# anglesenseor.net
KiCad netlist of a schematic drawn in EAGLE
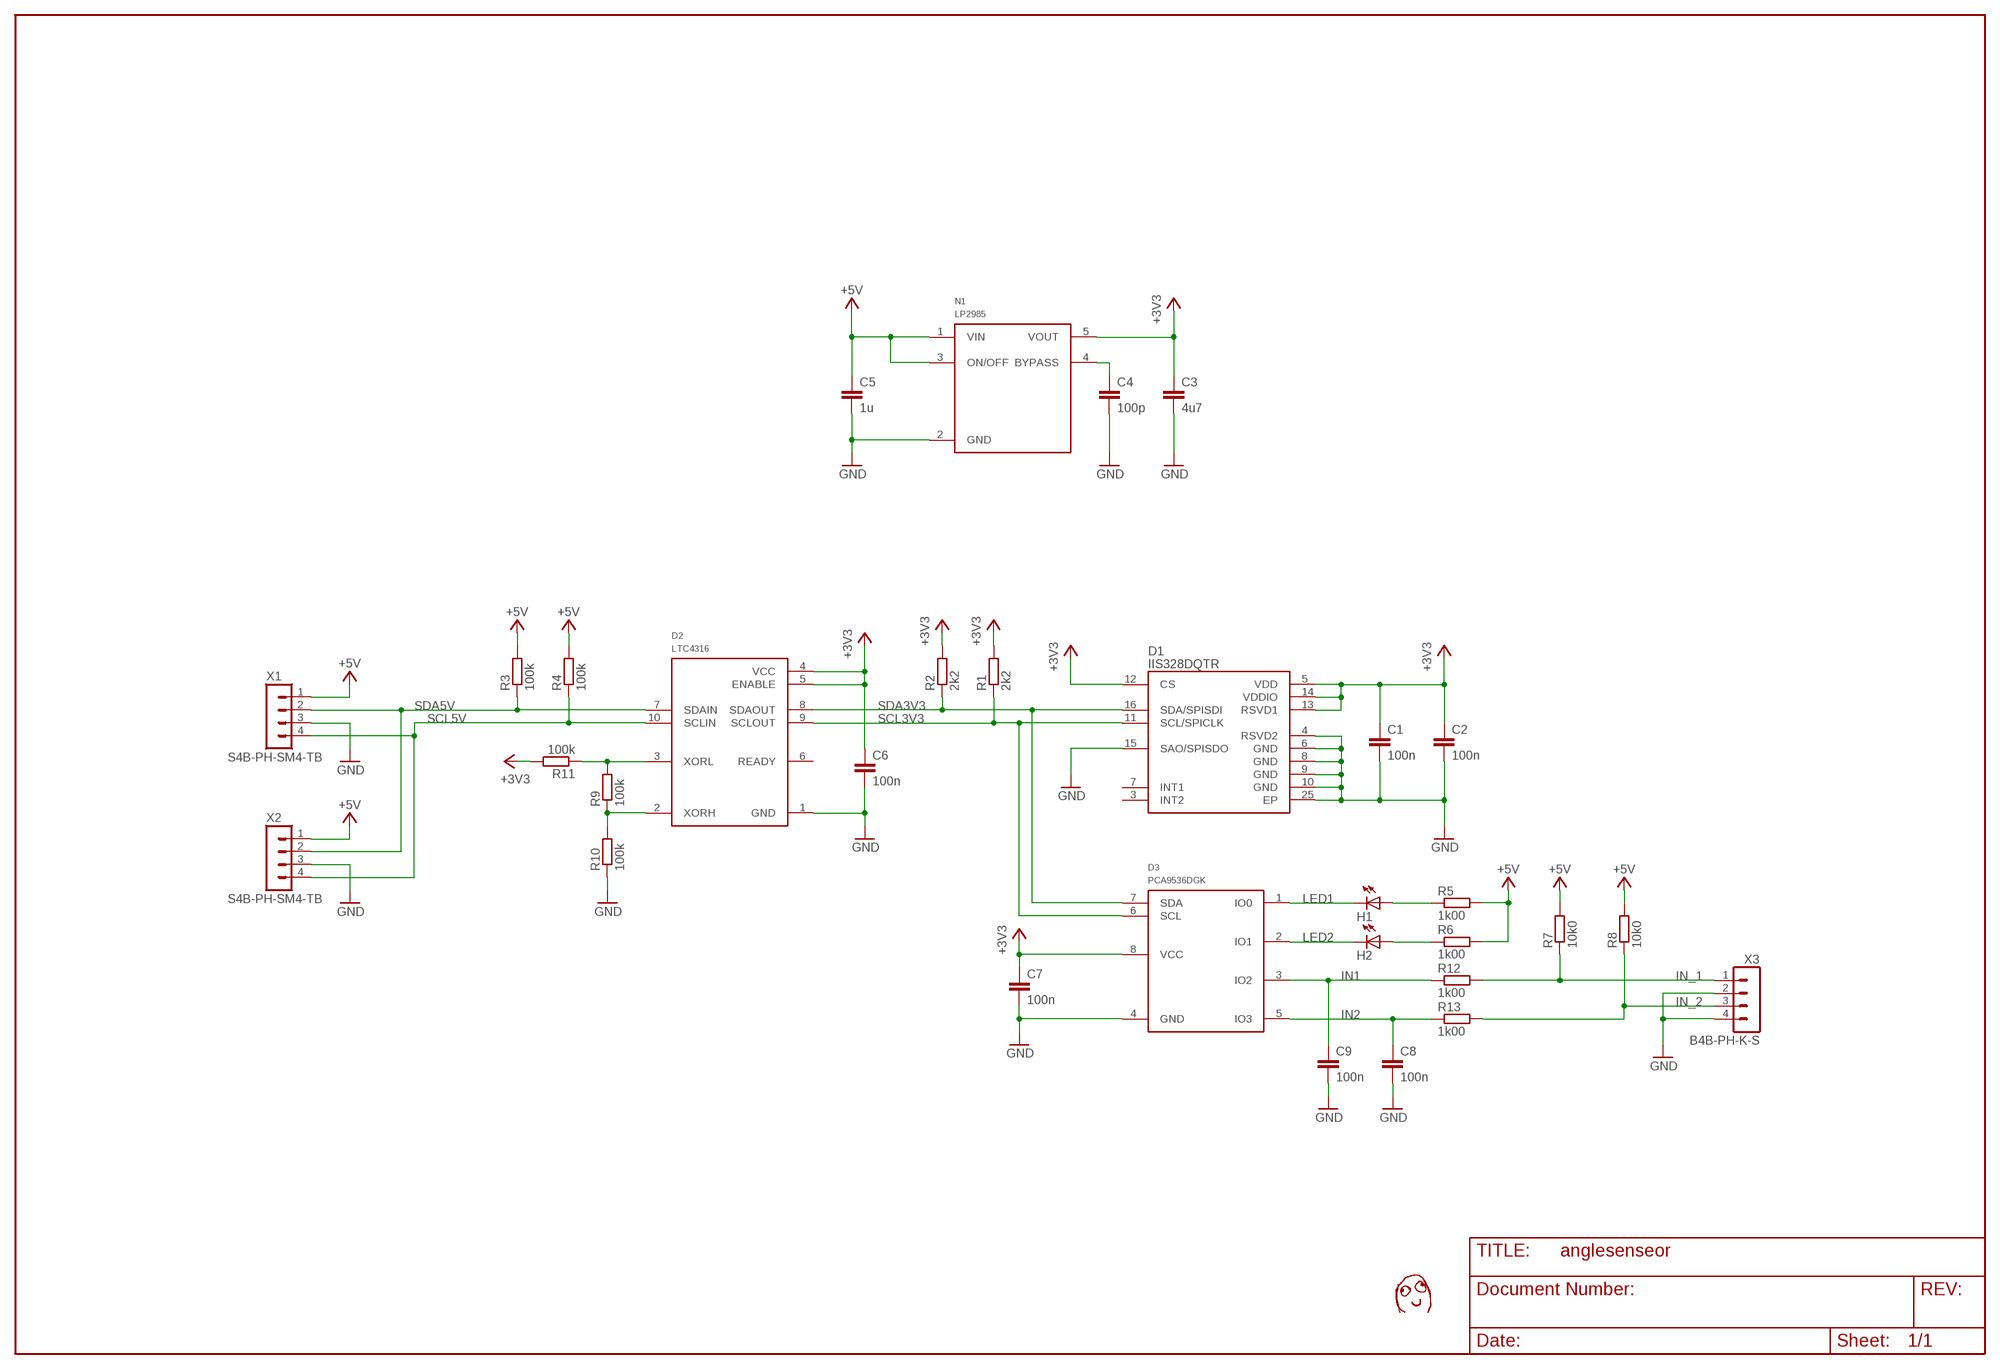
[diagram p0: schematic, sheet 1]

(export (version "E")
  (design (tool "Eeschema 10.0.6"))
  (components
    (comp (ref "C1")
      (value "100n")
      (footprint "eagle-import:C0603")
      (libsource (lib "eagle-import") (part "passiivit_CAP0603"))
    )
    (comp (ref "C2")
      (value "100n")
      (footprint "eagle-import:C0603")
      (libsource (lib "eagle-import") (part "passiivit_CAP0603"))
    )
    (comp (ref "C3")
      (value "4u7")
      (footprint "eagle-import:OMAT_IC_2_C0805")
      (libsource (lib "eagle-import") (part "CAP0805"))
    )
    (comp (ref "C4")
      (value "100p")
      (footprint "eagle-import:OMAT_IC_2_C0603")
      (libsource (lib "eagle-import") (part "CAP0603"))
    )
    (comp (ref "C5")
      (value "1u")
      (footprint "eagle-import:OMAT_IC_2_C0603")
      (libsource (lib "eagle-import") (part "CAP0603"))
    )
    (comp (ref "C6")
      (value "100n")
      (footprint "eagle-import:C0603")
      (libsource (lib "eagle-import") (part "passiivit_CAP0603"))
    )
    (comp (ref "C7")
      (value "100n")
      (footprint "eagle-import:C0603")
      (libsource (lib "eagle-import") (part "passiivit_CAP0603"))
    )
    (comp (ref "C8")
      (value "100n")
      (footprint "eagle-import:C0603")
      (libsource (lib "eagle-import") (part "passiivit_CAP0603"))
    )
    (comp (ref "C9")
      (value "100n")
      (footprint "eagle-import:C0603")
      (libsource (lib "eagle-import") (part "passiivit_CAP0603"))
    )
    (comp (ref "D1")
      (value "IIS328DQTR")
      (footprint "eagle-import:QFN50P400X400X100-25N")
      (libsource (lib "eagle-import") (part "IIS328DQTR"))
    )
    (comp (ref "D2")
      (value "LTC4316")
      (footprint "eagle-import:MSOP-10")
      (libsource (lib "eagle-import") (part "LTC4316"))
    )
    (comp (ref "D3")
      (value "PCA9536DGK")
      (footprint "eagle-import:TSSOP8-66")
      (libsource (lib "eagle-import") (part "PCA9536DGK"))
    )
    (comp (ref "H1")
      (value "LEDCHIPLED_0603")
      (footprint "eagle-import:CHIPLED_0603")
      (libsource (lib "eagle-import") (part "LEDCHIPLED_0603"))
    )
    (comp (ref "H2")
      (value "LEDCHIPLED_0603")
      (footprint "eagle-import:CHIPLED_0603")
      (libsource (lib "eagle-import") (part "LEDCHIPLED_0603"))
    )
    (comp (ref "N1")
      (value "LP2985")
      (footprint "eagle-import:SOT95P280X145-5N")
      (libsource (lib "eagle-import") (part "LP2985"))
    )
    (comp (ref "R1")
      (value "2k2")
      (footprint "eagle-import:R0603")
      (libsource (lib "eagle-import") (part "RES0603"))
    )
    (comp (ref "R2")
      (value "2k2")
      (footprint "eagle-import:R0603")
      (libsource (lib "eagle-import") (part "RES0603"))
    )
    (comp (ref "R3")
      (value "100k")
      (footprint "eagle-import:R0603")
      (libsource (lib "eagle-import") (part "RES0603"))
    )
    (comp (ref "R4")
      (value "100k")
      (footprint "eagle-import:R0603")
      (libsource (lib "eagle-import") (part "RES0603"))
    )
    (comp (ref "R5")
      (value "1k00")
      (footprint "eagle-import:R0603")
      (libsource (lib "eagle-import") (part "RES0603"))
    )
    (comp (ref "R6")
      (value "1k00")
      (footprint "eagle-import:R0603")
      (libsource (lib "eagle-import") (part "RES0603"))
    )
    (comp (ref "R7")
      (value "10k0")
      (footprint "eagle-import:R0603")
      (libsource (lib "eagle-import") (part "RES0603"))
    )
    (comp (ref "R8")
      (value "10k0")
      (footprint "eagle-import:R0603")
      (libsource (lib "eagle-import") (part "RES0603"))
    )
    (comp (ref "R9")
      (value "100k")
      (footprint "eagle-import:R0603")
      (libsource (lib "eagle-import") (part "RES0603"))
    )
    (comp (ref "R10")
      (value "100k")
      (footprint "eagle-import:R0603")
      (libsource (lib "eagle-import") (part "RES0603"))
    )
    (comp (ref "R11")
      (value "100k")
      (footprint "eagle-import:R0603")
      (libsource (lib "eagle-import") (part "RES0603"))
    )
    (comp (ref "R12")
      (value "1k00")
      (footprint "eagle-import:R0603")
      (libsource (lib "eagle-import") (part "RES0603"))
    )
    (comp (ref "R13")
      (value "1k00")
      (footprint "eagle-import:R0603")
      (libsource (lib "eagle-import") (part "RES0603"))
    )
    (comp (ref "U$1")
      (value "DAFUG")
      (footprint "eagle-import:DAFUG")
      (libsource (lib "eagle-import") (part "DAFUG"))
    )
    (comp (ref "X1")
      (value "S4B-PH-SM4-TB")
      (footprint "eagle-import:JST-PH2.0-RA-4")
      (libsource (lib "eagle-import") (part "S4B-PH-SM4-TB"))
    )
    (comp (ref "X2")
      (value "S4B-PH-SM4-TB")
      (footprint "eagle-import:JST-PH2.0-RA-4")
      (libsource (lib "eagle-import") (part "S4B-PH-SM4-TB"))
    )
    (comp (ref "X3")
      (value "B4B-PH-K-S")
      (footprint "eagle-import:B4B-PH-K-S")
      (libsource (lib "eagle-import") (part "B4B-PH-K-S"))
    )
  )
  (nets
    (net (code "1") (name "+3V3") (class "Default")
      (node (ref "C1") (pin "1") (pinfunction "1_1") (pintype "passive"))
      (node (ref "C2") (pin "1") (pinfunction "1_1") (pintype "passive"))
      (node (ref "C3") (pin "1") (pinfunction "1_1") (pintype "passive"))
      (node (ref "C6") (pin "1") (pinfunction "1_1") (pintype "passive"))
      (node (ref "C7") (pin "1") (pinfunction "1_1") (pintype "passive"))
      (node (ref "D1") (pin "12") (pinfunction "CS_12") (pintype "bidirectional"))
      (node (ref "D1") (pin "13") (pinfunction "RSVD1_13") (pintype "bidirectional"))
      (node (ref "D1") (pin "14") (pinfunction "VDDIO_14") (pintype "bidirectional"))
      (node (ref "D1") (pin "5") (pinfunction "VDD_5") (pintype "bidirectional"))
      (node (ref "D2") (pin "4") (pinfunction "VCC_4") (pintype "bidirectional"))
      (node (ref "D2") (pin "5") (pinfunction "ENABLE_5") (pintype "bidirectional"))
      (node (ref "D3") (pin "8") (pinfunction "VCC_8") (pintype "bidirectional"))
      (node (ref "N1") (pin "5") (pinfunction "VOUT_5") (pintype "bidirectional"))
      (node (ref "R1") (pin "2") (pinfunction "2_2") (pintype "passive"))
      (node (ref "R11") (pin "2") (pinfunction "2_2") (pintype "passive"))
      (node (ref "R2") (pin "2") (pinfunction "2_2") (pintype "passive"))
    )
    (net (code "2") (name "+5V") (class "Default")
      (node (ref "C5") (pin "1") (pinfunction "1_1") (pintype "passive"))
      (node (ref "N1") (pin "1") (pinfunction "VIN_1") (pintype "bidirectional"))
      (node (ref "N1") (pin "3") (pinfunction "ON/OFF_3") (pintype "bidirectional"))
      (node (ref "R3") (pin "2") (pinfunction "2_2") (pintype "passive"))
      (node (ref "R4") (pin "2") (pinfunction "2_2") (pintype "passive"))
      (node (ref "R5") (pin "2") (pinfunction "2_2") (pintype "passive"))
      (node (ref "R6") (pin "2") (pinfunction "2_2") (pintype "passive"))
      (node (ref "R7") (pin "2") (pinfunction "2_2") (pintype "passive"))
      (node (ref "R8") (pin "2") (pinfunction "2_2") (pintype "passive"))
      (node (ref "X1") (pin "1") (pinfunction "1_1") (pintype "passive"))
      (node (ref "X2") (pin "1") (pinfunction "1_1") (pintype "passive"))
    )
    (net (code "3") (name "/IN1") (class "Default")
      (node (ref "C9") (pin "1") (pinfunction "1_1") (pintype "passive"))
      (node (ref "D3") (pin "3") (pinfunction "IO2_3") (pintype "bidirectional"))
      (node (ref "R12") (pin "1") (pinfunction "1_1") (pintype "passive"))
    )
    (net (code "4") (name "/IN2") (class "Default")
      (node (ref "C8") (pin "1") (pinfunction "1_1") (pintype "passive"))
      (node (ref "D3") (pin "5") (pinfunction "IO3_5") (pintype "bidirectional"))
      (node (ref "R13") (pin "1") (pinfunction "1_1") (pintype "passive"))
    )
    (net (code "5") (name "/IN_1") (class "Default")
      (node (ref "R12") (pin "2") (pinfunction "2_2") (pintype "passive"))
      (node (ref "R7") (pin "1") (pinfunction "1_1") (pintype "passive"))
      (node (ref "X3") (pin "1") (pinfunction "1_1") (pintype "passive"))
    )
    (net (code "6") (name "/IN_2") (class "Default")
      (node (ref "R13") (pin "2") (pinfunction "2_2") (pintype "passive"))
      (node (ref "R8") (pin "1") (pinfunction "1_1") (pintype "passive"))
      (node (ref "X3") (pin "3") (pinfunction "3_3") (pintype "passive"))
    )
    (net (code "7") (name "/LED1") (class "Default")
      (node (ref "D3") (pin "1") (pinfunction "IO0_1") (pintype "bidirectional"))
      (node (ref "H1") (pin "C") (pinfunction "C_C") (pintype "passive"))
    )
    (net (code "8") (name "/LED2") (class "Default")
      (node (ref "D3") (pin "2") (pinfunction "IO1_2") (pintype "bidirectional"))
      (node (ref "H2") (pin "C") (pinfunction "C_C") (pintype "passive"))
    )
    (net (code "9") (name "/SCL3V3") (class "Default")
      (node (ref "D1") (pin "11") (pinfunction "SCL/SPICLK_11") (pintype "bidirectional"))
      (node (ref "D2") (pin "9") (pinfunction "SCLOUT_9") (pintype "bidirectional"))
      (node (ref "D3") (pin "6") (pinfunction "SCL_6") (pintype "bidirectional"))
      (node (ref "R1") (pin "1") (pinfunction "1_1") (pintype "passive"))
    )
    (net (code "10") (name "/SCL5V") (class "Default")
      (node (ref "D2") (pin "10") (pinfunction "SCLIN_10") (pintype "bidirectional"))
      (node (ref "R4") (pin "1") (pinfunction "1_1") (pintype "passive"))
      (node (ref "X1") (pin "4") (pinfunction "4_4") (pintype "passive"))
      (node (ref "X2") (pin "4") (pinfunction "4_4") (pintype "passive"))
    )
    (net (code "11") (name "/SDA3V3") (class "Default")
      (node (ref "D1") (pin "16") (pinfunction "SDA/SPISDI_16") (pintype "bidirectional"))
      (node (ref "D2") (pin "8") (pinfunction "SDAOUT_8") (pintype "bidirectional"))
      (node (ref "D3") (pin "7") (pinfunction "SDA_7") (pintype "bidirectional"))
      (node (ref "R2") (pin "1") (pinfunction "1_1") (pintype "passive"))
    )
    (net (code "12") (name "/SDA5V") (class "Default")
      (node (ref "D2") (pin "7") (pinfunction "SDAIN_7") (pintype "bidirectional"))
      (node (ref "R3") (pin "1") (pinfunction "1_1") (pintype "passive"))
      (node (ref "X1") (pin "2") (pinfunction "2_2") (pintype "passive"))
      (node (ref "X2") (pin "2") (pinfunction "2_2") (pintype "passive"))
    )
    (net (code "13") (name "GND") (class "Default")
      (node (ref "C1") (pin "2") (pinfunction "2_2") (pintype "passive"))
      (node (ref "C2") (pin "2") (pinfunction "2_2") (pintype "passive"))
      (node (ref "C3") (pin "2") (pinfunction "2_2") (pintype "passive"))
      (node (ref "C4") (pin "2") (pinfunction "2_2") (pintype "passive"))
      (node (ref "C5") (pin "2") (pinfunction "2_2") (pintype "passive"))
      (node (ref "C6") (pin "2") (pinfunction "2_2") (pintype "passive"))
      (node (ref "C7") (pin "2") (pinfunction "2_2") (pintype "passive"))
      (node (ref "C8") (pin "2") (pinfunction "2_2") (pintype "passive"))
      (node (ref "C9") (pin "2") (pinfunction "2_2") (pintype "passive"))
      (node (ref "D1") (pin "10") (pinfunction "GND_10") (pintype "bidirectional"))
      (node (ref "D1") (pin "15") (pinfunction "SAO/SPISDO_15") (pintype "bidirectional"))
      (node (ref "D1") (pin "25") (pinfunction "EP_25") (pintype "bidirectional"))
      (node (ref "D1") (pin "4") (pinfunction "RSVD2_4") (pintype "bidirectional"))
      (node (ref "D1") (pin "6") (pinfunction "GND_6") (pintype "bidirectional"))
      (node (ref "D1") (pin "8") (pinfunction "GND_8") (pintype "bidirectional"))
      (node (ref "D1") (pin "9") (pinfunction "GND_9") (pintype "bidirectional"))
      (node (ref "D2") (pin "1") (pinfunction "GND_1") (pintype "bidirectional"))
      (node (ref "D3") (pin "4") (pinfunction "GND_4") (pintype "bidirectional"))
      (node (ref "N1") (pin "2") (pinfunction "GND_2") (pintype "bidirectional"))
      (node (ref "R10") (pin "1") (pinfunction "1_1") (pintype "passive"))
      (node (ref "X1") (pin "3") (pinfunction "3_3") (pintype "passive"))
      (node (ref "X2") (pin "3") (pinfunction "3_3") (pintype "passive"))
      (node (ref "X3") (pin "2") (pinfunction "2_2") (pintype "passive"))
      (node (ref "X3") (pin "4") (pinfunction "4_4") (pintype "passive"))
    )
    (net (code "14") (name "Net-(D2-XORH)") (class "Default")
      (node (ref "D2") (pin "2") (pinfunction "XORH_2") (pintype "bidirectional"))
      (node (ref "R10") (pin "2") (pinfunction "2_2") (pintype "passive"))
      (node (ref "R9") (pin "1") (pinfunction "1_1") (pintype "passive"))
    )
    (net (code "15") (name "Net-(D2-XORL)") (class "Default")
      (node (ref "D2") (pin "3") (pinfunction "XORL_3") (pintype "bidirectional"))
      (node (ref "R11") (pin "1") (pinfunction "1_1") (pintype "passive"))
      (node (ref "R9") (pin "2") (pinfunction "2_2") (pintype "passive"))
    )
    (net (code "16") (name "Net-(H1-PadA)") (class "Default")
      (node (ref "H1") (pin "A") (pinfunction "A_A") (pintype "passive"))
      (node (ref "R5") (pin "1") (pinfunction "1_1") (pintype "passive"))
    )
    (net (code "17") (name "Net-(H2-PadA)") (class "Default")
      (node (ref "H2") (pin "A") (pinfunction "A_A") (pintype "passive"))
      (node (ref "R6") (pin "1") (pinfunction "1_1") (pintype "passive"))
    )
    (net (code "18") (name "Net-(N1-BYPASS)") (class "Default")
      (node (ref "C4") (pin "1") (pinfunction "1_1") (pintype "passive"))
      (node (ref "N1") (pin "4") (pinfunction "BYPASS_4") (pintype "bidirectional"))
    )
    (net (code "19") (name "unconnected-(D1-INT1-Pad7)") (class "Default")
      (node (ref "D1") (pin "7") (pinfunction "INT1_7") (pintype "bidirectional"))
    )
    (net (code "20") (name "unconnected-(D1-INT2-Pad3)") (class "Default")
      (node (ref "D1") (pin "3") (pinfunction "INT2_3") (pintype "bidirectional"))
    )
    (net (code "21") (name "unconnected-(D2-READY-Pad6)") (class "Default")
      (node (ref "D2") (pin "6") (pinfunction "READY_6") (pintype "bidirectional"))
    )
  )
)
